# LV8121V.net
KiCad netlist of a schematic drawn in Altium Designer
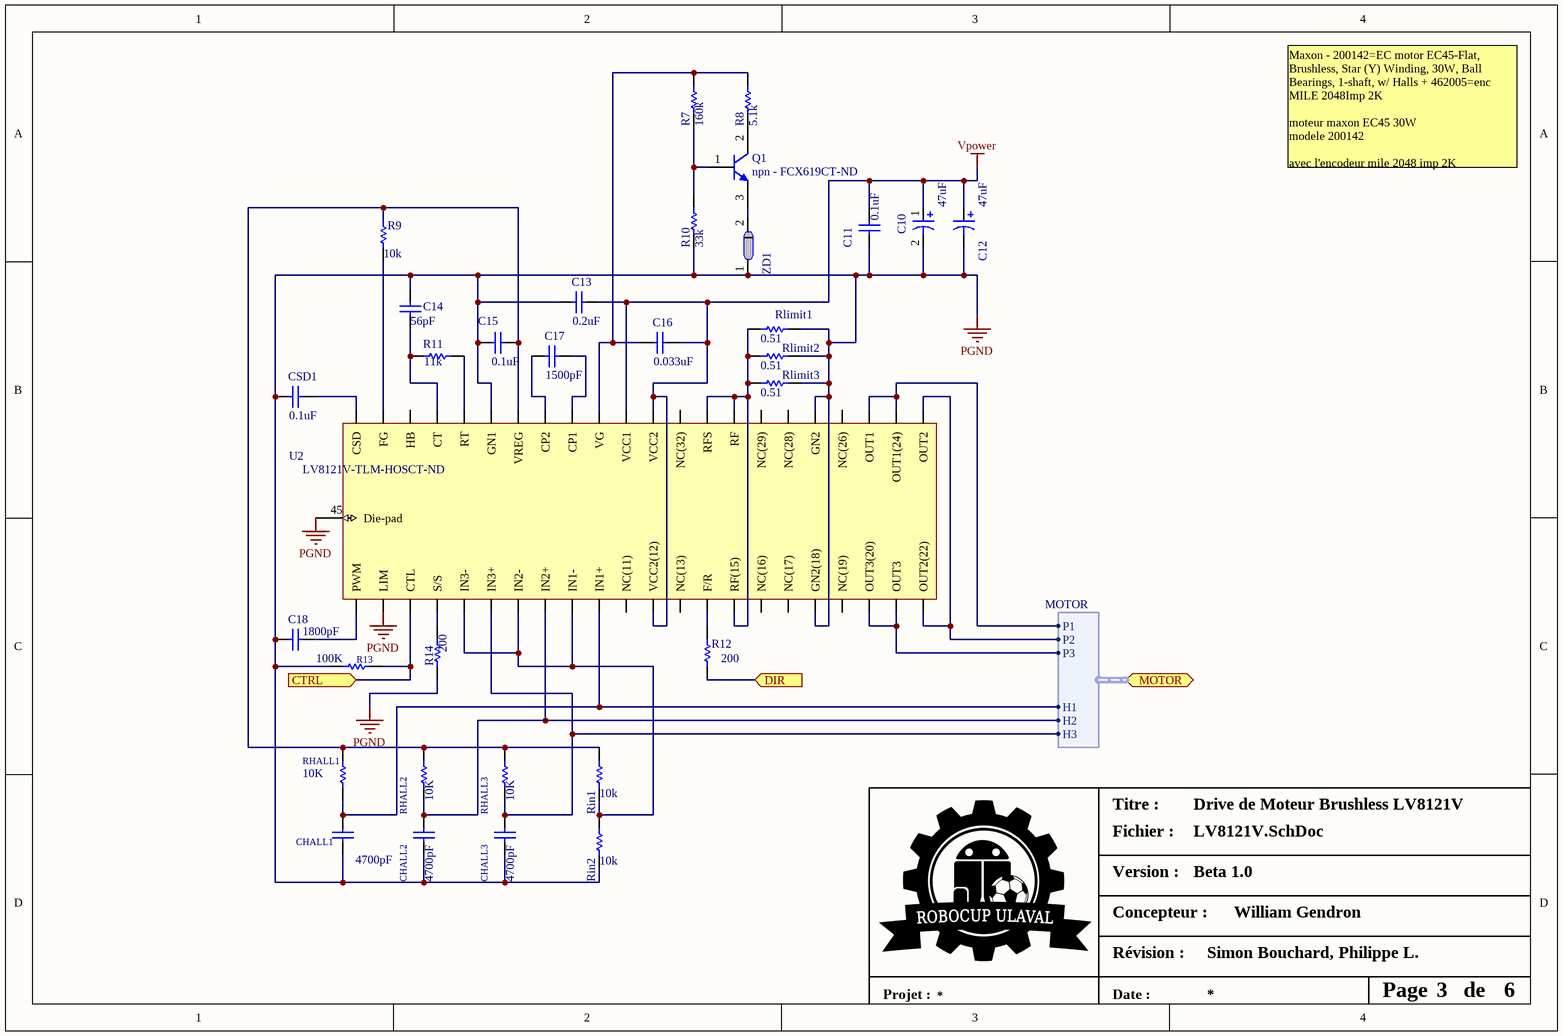
[diagram p0: LV8121V.SchDoc]

(export (version "E")
  (design (tool "Eeschema 10.0.6"))
  (components
    (comp (ref "C10")
      (value "47uF")
      (footprint "sidecap_47uf")
      (description "Polarized Capacitor (Radial)")
      (fields (field (name "Comment") "47uf - P13464-ND"))
      (libsource (lib "") (part "Cap Pol1_1"))
    )
    (comp (ref "C11")
      (value "0.1uF")
      (footprint "c1206")
      (description "Capacitor")
      (fields (field (name "Comment") ".1uf - 399-1249-1-ND"))
      (libsource (lib "Miscellaneous Devices") (part "Cap"))
    )
    (comp (ref "C12")
      (value "47uF")
      (footprint "sidecap_47uf_rev")
      (description "Polarized Capacitor (Radial)")
      (fields (field (name "Comment") "47uf - P13464-ND"))
      (libsource (lib "Miscellaneous Devices") (part "Cap Pol1"))
    )
    (comp (ref "C13")
      (value "0.2uF")
      (footprint "c1206")
      (description "Capacitor")
      (fields (field (name "Comment") "0.2uf - 399-1251-1-ND"))
      (libsource (lib "Miscellaneous Devices") (part "Cap"))
    )
    (comp (ref "C14")
      (value "56pF")
      (footprint "c1206")
      (description "Capacitor")
      (fields (field (name "Comment") "56pf - 399-1203-1-ND"))
      (libsource (lib "Miscellaneous Devices") (part "Cap"))
    )
    (comp (ref "C15")
      (value "0.1uF")
      (footprint "c1206")
      (description "Capacitor")
      (fields (field (name "Comment") "0.1uf  - 399-1249-1-ND"))
      (libsource (lib "Miscellaneous Devices") (part "Cap"))
    )
    (comp (ref "C16")
      (value "0.033uF")
      (footprint "c1206")
      (description "Capacitor")
      (fields (field (name "Comment") "0.033uf - 1276-1289-1-ND"))
      (libsource (lib "Miscellaneous Devices") (part "Cap"))
    )
    (comp (ref "C17")
      (value "1500pF")
      (footprint "c1206")
      (description "Capacitor")
      (fields (field (name "Comment") "1500pf - 399-1224-1-ND"))
      (libsource (lib "Miscellaneous Devices") (part "Cap"))
    )
    (comp (ref "C18")
      (value "1800pF")
      (footprint "c1206")
      (description "Capacitor")
      (fields (field (name "Comment") "1800pf - 399-1225-1-ND"))
      (libsource (lib "Miscellaneous Devices") (part "Cap"))
    )
    (comp (ref "CHALL1")
      (value "4700pF")
      (footprint "c1206")
      (description "Capacitor")
      (fields (field (name "Comment") "4700pf - 445-2333-1-ND"))
      (libsource (lib "Miscellaneous Devices") (part "Cap"))
    )
    (comp (ref "CHALL2")
      (value "4700pF")
      (footprint "c1206")
      (description "Capacitor")
      (fields (field (name "Comment") "4700pf -445-2333-1-ND"))
      (libsource (lib "Miscellaneous Devices") (part "Cap"))
    )
    (comp (ref "CHALL3")
      (value "4700pF")
      (footprint "c1206")
      (description "Capacitor")
      (fields (field (name "Comment") "4700pf - 445-2333-1-ND"))
      (libsource (lib "Miscellaneous Devices") (part "Cap"))
    )
    (comp (ref "CSD1")
      (value "0.1uF")
      (footprint "c1206")
      (description "Capacitor")
      (fields (field (name "Comment") "0.1uf - 399-1249-1-ND"))
      (libsource (lib "Miscellaneous Devices") (part "Cap"))
    )
    (comp (ref "Q1")
      (value "npn - FCX619CT-ND")
      (footprint "PLZZ0004CA-A_N")
      (description "Silicon NPN Epitaxial, UHF / VHF Wide Band Amplifier")
      (libsource (lib "2sc5964") (part "2SC5964"))
    )
    (comp (ref "R7")
      (value "160k")
      (footprint "c1206")
      (description "Resistor")
      (fields (field (name "Comment") "160k - 311-160KERCT-ND"))
      (libsource (lib "Miscellaneous Devices") (part "Res1"))
    )
    (comp (ref "R8")
      (value "5.1k")
      (footprint "c1206")
      (description "Resistor")
      (fields (field (name "Comment") "5.1k - P5.10KFCT-ND"))
      (libsource (lib "Miscellaneous Devices") (part "Res1"))
    )
    (comp (ref "R9")
      (value "10k")
      (footprint "c1206")
      (description "Resistor")
      (fields (field (name "Comment") "10K - 311-10.0KFRCT-ND") (field (name "PUBLISHER") "Altium Limited"))
      (libsource (lib "Miscellaneous Devices") (part "Res1"))
    )
    (comp (ref "R10")
      (value "33k")
      (footprint "c1206")
      (description "Resistor")
      (fields (field (name "Comment") "33k - 311-33KERCT-ND"))
      (libsource (lib "Miscellaneous Devices") (part "Res1"))
    )
    (comp (ref "R11")
      (value "11k")
      (footprint "C1206")
      (description "Resistor")
      (fields (field (name "Comment") "11k - 311-11.5KFRCT-ND"))
      (libsource (lib "Miscellaneous Devices") (part "Res1"))
    )
    (comp (ref "R12")
      (value "200")
      (footprint "c1206")
      (description "Resistor")
      (fields (field (name "Comment") "200ohms - 311-200FRCT-ND"))
      (libsource (lib "Miscellaneous Devices") (part "Res1"))
    )
    (comp (ref "R13")
      (value "100K")
      (footprint "c1206")
      (description "Resistor")
      (fields (field (name "Comment") "100k - 311-100KFRCT-ND"))
      (libsource (lib "Miscellaneous Devices") (part "Res1"))
    )
    (comp (ref "R14")
      (value "200")
      (footprint "c1206")
      (description "Resistor")
      (fields (field (name "Comment") "200ohms - 311-200FRCT-ND"))
      (libsource (lib "Miscellaneous Devices") (part "Res1"))
    )
    (comp (ref "RHALL1")
      (value "10K")
      (footprint "c1206")
      (description "Resistor")
      (fields (field (name "Comment") "10k - 311-10.0KFRCT-ND"))
      (libsource (lib "Miscellaneous Devices") (part "Res1"))
    )
    (comp (ref "RHALL2")
      (value "10K")
      (footprint "c1206")
      (description "Resistor")
      (fields (field (name "Comment") "10k - 311-10.0KFRCT-ND"))
      (libsource (lib "Miscellaneous Devices") (part "Res1"))
    )
    (comp (ref "RHALL3")
      (value "10K")
      (footprint "c1206")
      (description "Resistor")
      (fields (field (name "Comment") "10k - 311-10.0KFRCT-ND"))
      (libsource (lib "Miscellaneous Devices") (part "Res1"))
    )
    (comp (ref "Rin1")
      (value "10k")
      (footprint "c1206")
      (description "Resistor")
      (fields (field (name "Comment") "10k - 311-10.0KFRCT-ND"))
      (libsource (lib "Miscellaneous Devices") (part "Res1"))
    )
    (comp (ref "Rin2")
      (value "10k")
      (footprint "c1206")
      (description "Resistor")
      (fields (field (name "Comment") "10k - 311-10.0KFRCT-ND"))
      (libsource (lib "Miscellaneous Devices") (part "Res1"))
    )
    (comp (ref "Rlimit1")
      (value "0.51")
      (footprint "c1206")
      (description "Resistor")
      (fields (field (name "Comment") "0.51ohms - 311-.51LWCT-ND"))
      (libsource (lib "Miscellaneous Devices") (part "Res1"))
    )
    (comp (ref "Rlimit2")
      (value "0.51")
      (footprint "c1206")
      (description "Resistor")
      (fields (field (name "Comment") "0.51 ohms - 311-.51LWCT-ND"))
      (libsource (lib "Miscellaneous Devices") (part "Res1"))
    )
    (comp (ref "Rlimit3")
      (value "0.51")
      (footprint "c1206")
      (description "Resistor")
      (fields (field (name "Comment") "0.51ohms - 311-.51LWCT-ND"))
      (libsource (lib "Miscellaneous Devices") (part "Res1"))
    )
    (comp (ref "U2")
      (value "LV8121V-TLM-HOSCT-ND")
      (footprint "LV8121V_update")
      (libsource (lib "LV8121V") (part "LV8121V"))
    )
    (comp (ref "ZD1")
      (value "zener 5.6V - CZRNC55C5V6-G-ND")
      (footprint "c1206")
      (libsource (lib "sod523_zener") (part "Component_1"))
    )
  )
  (nets
    (net (code "2") (name "/CTRL") (class "Default")
      (node (ref "R13") (pin "2") (pinfunction "2_2") (pintype "passive"))
      (node (ref "U2") (pin "3") (pinfunction "CTL_3") (pintype "bidirectional"))
    )
    (net (code "3") (name "/DIR") (class "Default")
      (node (ref "R12") (pin "1") (pinfunction "1_1") (pintype "passive"))
    )
    (net (code "5") (name "Net-(Q1-B)") (class "Default")
      (node (ref "Q1") (pin "1") (pinfunction "B_1") (pintype "passive"))
      (node (ref "R10") (pin "2") (pinfunction "2_2") (pintype "passive"))
      (node (ref "R7") (pin "1") (pinfunction "1_1") (pintype "passive"))
    )
    (net (code "6") (name "Net-(Q1-C)") (class "Default")
      (node (ref "Q1") (pin "2") (pinfunction "C_2") (pintype "passive"))
      (node (ref "R8") (pin "1") (pinfunction "1_1") (pintype "passive"))
    )
    (net (code "7") (name "Net-(Q1-E)") (class "Default")
      (node (ref "Q1") (pin "3") (pinfunction "E_3") (pintype "passive"))
      (node (ref "ZD1") (pin "2") (pinfunction "Cathode_2") (pintype "passive"))
    )
    (net (code "8") (name "Net-(U2-CP1)") (class "Default")
      (node (ref "C17") (pin "2") (pinfunction "2_2") (pintype "passive"))
      (node (ref "U2") (pin "36") (pinfunction "CP1_36") (pintype "bidirectional"))
    )
    (net (code "9") (name "Net-(U2-CP2)") (class "Default")
      (node (ref "C17") (pin "1") (pinfunction "1_1") (pintype "passive"))
      (node (ref "U2") (pin "37") (pinfunction "CP2_37") (pintype "bidirectional"))
    )
    (net (code "10") (name "Net-(U2-CSD)") (class "Default")
      (node (ref "CSD1") (pin "2") (pinfunction "2_2") (pintype "passive"))
      (node (ref "U2") (pin "44") (pinfunction "CSD_44") (pintype "bidirectional"))
    )
    (net (code "11") (name "Net-(U2-CT)") (class "Default")
      (node (ref "C14") (pin "1") (pinfunction "1_1") (pintype "passive"))
      (node (ref "R11") (pin "1") (pinfunction "1_1") (pintype "passive"))
      (node (ref "U2") (pin "41") (pinfunction "CT_41") (pintype "bidirectional"))
    )
    (net (code "12") (name "Net-(U2-FG)") (class "Default")
      (node (ref "R9") (pin "1") (pinfunction "1_1") (pintype "passive"))
      (node (ref "U2") (pin "43") (pinfunction "FG_43") (pintype "bidirectional"))
    )
    (net (code "13") (name "Net-(U2-F{slash}R)") (class "Default")
      (node (ref "R12") (pin "2") (pinfunction "2_2") (pintype "passive"))
      (node (ref "U2") (pin "14") (pinfunction "F/R_14") (pintype "bidirectional"))
    )
    (net (code "14") (name "Net-(U2-IN1+)") (class "Default")
      (node (ref "CHALL1") (pin "2") (pinfunction "2_2") (pintype "passive"))
      (node (ref "RHALL1") (pin "1") (pinfunction "1_1") (pintype "passive"))
      (node (ref "U2") (pin "10") (pinfunction "IN1+_10") (pintype "bidirectional"))
    )
    (net (code "15") (name "Net-(U2-IN1-)") (class "Default")
      (node (ref "Rin1") (pin "1") (pinfunction "1_1") (pintype "passive"))
      (node (ref "Rin2") (pin "2") (pinfunction "2_2") (pintype "passive"))
      (node (ref "U2") (pin "5") (pinfunction "IN3-_5") (pintype "bidirectional"))
      (node (ref "U2") (pin "7") (pinfunction "IN2-_7") (pintype "bidirectional"))
      (node (ref "U2") (pin "9") (pinfunction "IN1-_9") (pintype "bidirectional"))
    )
    (net (code "16") (name "Net-(U2-IN2+)") (class "Default")
      (node (ref "CHALL2") (pin "2") (pinfunction "2_2") (pintype "passive"))
      (node (ref "RHALL2") (pin "1") (pinfunction "1_1") (pintype "passive"))
      (node (ref "U2") (pin "8") (pinfunction "IN2+_8") (pintype "bidirectional"))
    )
    (net (code "17") (name "Net-(U2-IN3+)") (class "Default")
      (node (ref "CHALL3") (pin "2") (pinfunction "2_2") (pintype "passive"))
      (node (ref "RHALL3") (pin "1") (pinfunction "1_1") (pintype "passive"))
      (node (ref "U2") (pin "6") (pinfunction "IN3+_6") (pintype "bidirectional"))
    )
    (net (code "18") (name "Net-(U2-OUT1(24))") (class "Default")
      (node (ref "U2") (pin "24") (pinfunction "OUT1(24)_24") (pintype "bidirectional"))
      (node (ref "U2") (pin "25") (pinfunction "OUT1_25") (pintype "bidirectional"))
    )
    (net (code "19") (name "Net-(U2-OUT2(22))") (class "Default")
      (node (ref "U2") (pin "22") (pinfunction "OUT2(22)_22") (pintype "bidirectional"))
      (node (ref "U2") (pin "23") (pinfunction "OUT2_23") (pintype "bidirectional"))
    )
    (net (code "20") (name "Net-(U2-OUT3(20))") (class "Default")
      (node (ref "U2") (pin "20") (pinfunction "OUT3(20)_20") (pintype "bidirectional"))
      (node (ref "U2") (pin "21") (pinfunction "OUT3_21") (pintype "bidirectional"))
    )
    (net (code "21") (name "Net-(U2-PWM)") (class "Default")
      (node (ref "C18") (pin "2") (pinfunction "2_2") (pintype "passive"))
      (node (ref "U2") (pin "1") (pinfunction "PWM_1") (pintype "bidirectional"))
    )
    (net (code "22") (name "Net-(U2-RF(15))") (class "Default")
      (node (ref "Rlimit1") (pin "1") (pinfunction "1_1") (pintype "passive"))
      (node (ref "Rlimit2") (pin "1") (pinfunction "1_1") (pintype "passive"))
      (node (ref "Rlimit3") (pin "1") (pinfunction "1_1") (pintype "passive"))
      (node (ref "U2") (pin "15") (pinfunction "RF(15)_15") (pintype "bidirectional"))
      (node (ref "U2") (pin "30") (pinfunction "RF_30") (pintype "bidirectional"))
      (node (ref "U2") (pin "31") (pinfunction "RFS_31") (pintype "bidirectional"))
    )
    (net (code "23") (name "Net-(U2-RT)") (class "Default")
      (node (ref "R11") (pin "2") (pinfunction "2_2") (pintype "passive"))
      (node (ref "U2") (pin "40") (pinfunction "RT_40") (pintype "bidirectional"))
    )
    (net (code "24") (name "Net-(U2-S{slash}S)") (class "Default")
      (node (ref "R14") (pin "2") (pinfunction "2_2") (pintype "passive"))
      (node (ref "U2") (pin "4") (pinfunction "S/S_4") (pintype "bidirectional"))
    )
    (net (code "25") (name "Net-(U2-VG)") (class "Default")
      (node (ref "C16") (pin "1") (pinfunction "1_1") (pintype "passive"))
      (node (ref "R7") (pin "2") (pinfunction "2_2") (pintype "passive"))
      (node (ref "R8") (pin "2") (pinfunction "2_2") (pintype "passive"))
      (node (ref "U2") (pin "35") (pinfunction "VG_35") (pintype "bidirectional"))
    )
    (net (code "26") (name "Net-(U2-VREG)") (class "Default")
      (node (ref "C15") (pin "2") (pinfunction "2_2") (pintype "passive"))
      (node (ref "R9") (pin "2") (pinfunction "2_2") (pintype "passive"))
      (node (ref "RHALL1") (pin "2") (pinfunction "2_2") (pintype "passive"))
      (node (ref "RHALL2") (pin "2") (pinfunction "2_2") (pintype "passive"))
      (node (ref "RHALL3") (pin "2") (pinfunction "2_2") (pintype "passive"))
      (node (ref "Rin1") (pin "2") (pinfunction "2_2") (pintype "passive"))
      (node (ref "U2") (pin "38") (pinfunction "VREG_38") (pintype "bidirectional"))
    )
    (net (code "27") (name "PGND") (class "Default")
      (node (ref "C10") (pin "2") (pinfunction "2_2") (pintype "passive"))
      (node (ref "C11") (pin "1") (pinfunction "1_1") (pintype "passive"))
      (node (ref "C12") (pin "2") (pinfunction "2_2") (pintype "passive"))
      (node (ref "C13") (pin "1") (pinfunction "1_1") (pintype "passive"))
      (node (ref "C14") (pin "2") (pinfunction "2_2") (pintype "passive"))
      (node (ref "C15") (pin "1") (pinfunction "1_1") (pintype "passive"))
      (node (ref "C18") (pin "1") (pinfunction "1_1") (pintype "passive"))
      (node (ref "CHALL1") (pin "1") (pinfunction "1_1") (pintype "passive"))
      (node (ref "CHALL2") (pin "1") (pinfunction "1_1") (pintype "passive"))
      (node (ref "CHALL3") (pin "1") (pinfunction "1_1") (pintype "passive"))
      (node (ref "CSD1") (pin "1") (pinfunction "1_1") (pintype "passive"))
      (node (ref "R10") (pin "1") (pinfunction "1_1") (pintype "passive"))
      (node (ref "R13") (pin "1") (pinfunction "1_1") (pintype "passive"))
      (node (ref "R14") (pin "1") (pinfunction "1_1") (pintype "passive"))
      (node (ref "Rin2") (pin "1") (pinfunction "1_1") (pintype "passive"))
      (node (ref "Rlimit1") (pin "2") (pinfunction "2_2") (pintype "passive"))
      (node (ref "Rlimit2") (pin "2") (pinfunction "2_2") (pintype "passive"))
      (node (ref "Rlimit3") (pin "2") (pinfunction "2_2") (pintype "passive"))
      (node (ref "U2") (pin "18") (pinfunction "GN2(18)_18") (pintype "bidirectional"))
      (node (ref "U2") (pin "2") (pinfunction "LIM_2") (pintype "bidirectional"))
      (node (ref "U2") (pin "27") (pinfunction "GN2_27") (pintype "bidirectional"))
      (node (ref "U2") (pin "39") (pinfunction "GN1_39") (pintype "bidirectional"))
      (node (ref "U2") (pin "45") (pinfunction "Die-pad_45") (pintype "bidirectional"))
      (node (ref "ZD1") (pin "1") (pinfunction "Anode_1") (pintype "passive"))
    )
    (net (code "28") (name "Vpower") (class "Default")
      (node (ref "C10") (pin "1") (pinfunction "1_1") (pintype "passive"))
      (node (ref "C11") (pin "2") (pinfunction "2_2") (pintype "passive"))
      (node (ref "C12") (pin "1") (pinfunction "1_1") (pintype "passive"))
      (node (ref "C13") (pin "2") (pinfunction "2_2") (pintype "passive"))
      (node (ref "C16") (pin "2") (pinfunction "2_2") (pintype "passive"))
      (node (ref "U2") (pin "12") (pinfunction "VCC2(12)_12") (pintype "bidirectional"))
      (node (ref "U2") (pin "33") (pinfunction "VCC2_33") (pintype "bidirectional"))
      (node (ref "U2") (pin "34") (pinfunction "VCC1_34") (pintype "bidirectional"))
    )
    (net (code "29") (name "unconnected-(U2-HB-Pad42)") (class "Default")
      (node (ref "U2") (pin "42") (pinfunction "HB_42") (pintype "bidirectional"))
    )
    (net (code "30") (name "unconnected-(U2-NC(11)-Pad11)") (class "Default")
      (node (ref "U2") (pin "11") (pinfunction "NC(11)_11") (pintype "bidirectional"))
    )
    (net (code "31") (name "unconnected-(U2-NC(13)-Pad13)") (class "Default")
      (node (ref "U2") (pin "13") (pinfunction "NC(13)_13") (pintype "bidirectional"))
    )
    (net (code "32") (name "unconnected-(U2-NC(16)-Pad16)") (class "Default")
      (node (ref "U2") (pin "16") (pinfunction "NC(16)_16") (pintype "bidirectional"))
    )
    (net (code "33") (name "unconnected-(U2-NC(17)-Pad17)") (class "Default")
      (node (ref "U2") (pin "17") (pinfunction "NC(17)_17") (pintype "bidirectional"))
    )
    (net (code "34") (name "unconnected-(U2-NC(19)-Pad19)") (class "Default")
      (node (ref "U2") (pin "19") (pinfunction "NC(19)_19") (pintype "bidirectional"))
    )
    (net (code "35") (name "unconnected-(U2-NC(26)-Pad26)") (class "Default")
      (node (ref "U2") (pin "26") (pinfunction "NC(26)_26") (pintype "bidirectional"))
    )
    (net (code "36") (name "unconnected-(U2-NC(28)-Pad28)") (class "Default")
      (node (ref "U2") (pin "28") (pinfunction "NC(28)_28") (pintype "bidirectional"))
    )
    (net (code "37") (name "unconnected-(U2-NC(29)-Pad29)") (class "Default")
      (node (ref "U2") (pin "29") (pinfunction "NC(29)_29") (pintype "bidirectional"))
    )
    (net (code "38") (name "unconnected-(U2-NC(32)-Pad32)") (class "Default")
      (node (ref "U2") (pin "32") (pinfunction "NC(32)_32") (pintype "bidirectional"))
    )
  )
)
